# E17-07-TIU.net
KiCad netlist of a schematic drawn in Altium Designer
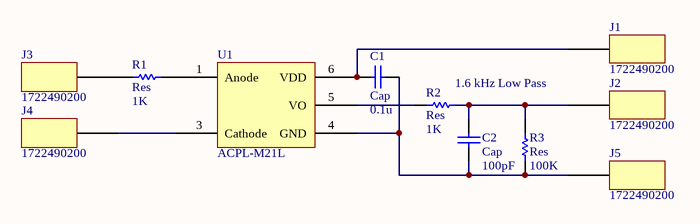
[diagram p0: E17-07-TIU.SchDoc]

(export (version "E")
  (design (tool "Eeschema 10.0.6"))
  (components
    (comp (ref "C1")
      (value "Cap")
      (footprint "C0805")
      (description "Capacitor")
      (fields (field (name "ALTIUM_VALUE") "0.1u") (field (name "PUBLISHER") "Altium Limited"))
      (libsource (lib "Capacitors") (part "Cap"))
    )
    (comp (ref "C2")
      (value "Cap")
      (footprint "C0805")
      (description "Capacitor")
      (fields (field (name "ALTIUM_VALUE") "100pF") (field (name "PUBLISHER") "Altium Limited"))
      (libsource (lib "Capacitors") (part "Cap"))
    )
    (comp (ref "J1")
      (value "1722490200")
      (footprint "1722490200")
      (libsource (lib "Connectors and Headers") (part "1722490200"))
    )
    (comp (ref "J2")
      (value "1722490200")
      (footprint "1722490200")
      (libsource (lib "Connectors and Headers") (part "1722490200"))
    )
    (comp (ref "J3") (value "1722490200") (footprint "1722490200") (libsource (lib "") (part "1722490200_1")))
    (comp (ref "J4") (value "1722490200") (footprint "1722490200") (libsource (lib "") (part "1722490200_1")))
    (comp (ref "J5")
      (value "1722490200")
      (footprint "1722490200")
      (libsource (lib "Connectors and Headers") (part "1722490200"))
    )
    (comp (ref "R1")
      (value "Res")
      (footprint "2012[0805]")
      (description "Surface Mount Resistor")
      (fields (field (name "ALTIUM_VALUE") "1K") (field (name "PUBLISHER") "Altium Limited"))
      (libsource (lib "Resistors") (part "Res"))
    )
    (comp (ref "R2")
      (value "Res")
      (footprint "2012[0805]")
      (description "Surface Mount Resistor")
      (fields (field (name "ALTIUM_VALUE") "1K") (field (name "PUBLISHER") "Altium Limited"))
      (libsource (lib "Resistors") (part "Res"))
    )
    (comp (ref "R3")
      (value "Res")
      (footprint "2012[0805]")
      (description "Surface Mount Resistor")
      (fields (field (name "ALTIUM_VALUE") "100K") (field (name "PUBLISHER") "Altium Limited"))
      (libsource (lib "Resistors") (part "Res"))
    )
    (comp (ref "U1")
      (value "ACPL-M21L")
      (footprint "ACPL-M21L")
      (libsource (lib "Isolation Circuits") (part "ACPL-M21L"))
    )
  )
  (nets
    (net (code "1") (name "Net-(C2-Pad2)") (class "Default")
      (node (ref "C2") (pin "2") (pinfunction "2_2") (pintype "passive"))
      (node (ref "J2") (pin "1") (pinfunction "1_1") (pintype "passive"))
      (node (ref "R2") (pin "2") (pinfunction "2_2") (pintype "passive"))
      (node (ref "R3") (pin "2") (pinfunction "2_2") (pintype "passive"))
    )
    (net (code "2") (name "Net-(J3-Pad1)") (class "Default")
      (node (ref "J3") (pin "1") (pinfunction "1_1") (pintype "passive"))
      (node (ref "R1") (pin "1") (pinfunction "1_1") (pintype "passive"))
    )
    (net (code "3") (name "Net-(U1-Anode)") (class "Default")
      (node (ref "R1") (pin "2") (pinfunction "2_2") (pintype "passive"))
      (node (ref "U1") (pin "1") (pinfunction "Anode_1") (pintype "passive"))
    )
    (net (code "4") (name "Net-(U1-Cathode)") (class "Default")
      (node (ref "J4") (pin "1") (pinfunction "1_1") (pintype "passive"))
      (node (ref "U1") (pin "3") (pinfunction "Cathode_3") (pintype "passive"))
    )
    (net (code "5") (name "Net-(U1-GND)") (class "Default")
      (node (ref "C1") (pin "1") (pinfunction "1_1") (pintype "passive"))
      (node (ref "C2") (pin "1") (pinfunction "1_1") (pintype "passive"))
      (node (ref "J5") (pin "1") (pinfunction "1_1") (pintype "passive"))
      (node (ref "R3") (pin "1") (pinfunction "1_1") (pintype "passive"))
      (node (ref "U1") (pin "4") (pinfunction "GND_4") (pintype "passive"))
    )
    (net (code "6") (name "Net-(U1-VDD)") (class "Default")
      (node (ref "C1") (pin "2") (pinfunction "2_2") (pintype "passive"))
      (node (ref "J1") (pin "1") (pinfunction "1_1") (pintype "passive"))
      (node (ref "U1") (pin "6") (pinfunction "VDD_6") (pintype "passive"))
    )
    (net (code "7") (name "Net-(U1-VO)") (class "Default")
      (node (ref "R2") (pin "1") (pinfunction "1_1") (pintype "passive"))
      (node (ref "U1") (pin "5") (pinfunction "VO_5") (pintype "passive"))
    )
  )
)
